# SCH_LED-Chaser_2025-12-01.net
KiCad netlist of a schematic drawn in EasyEDA
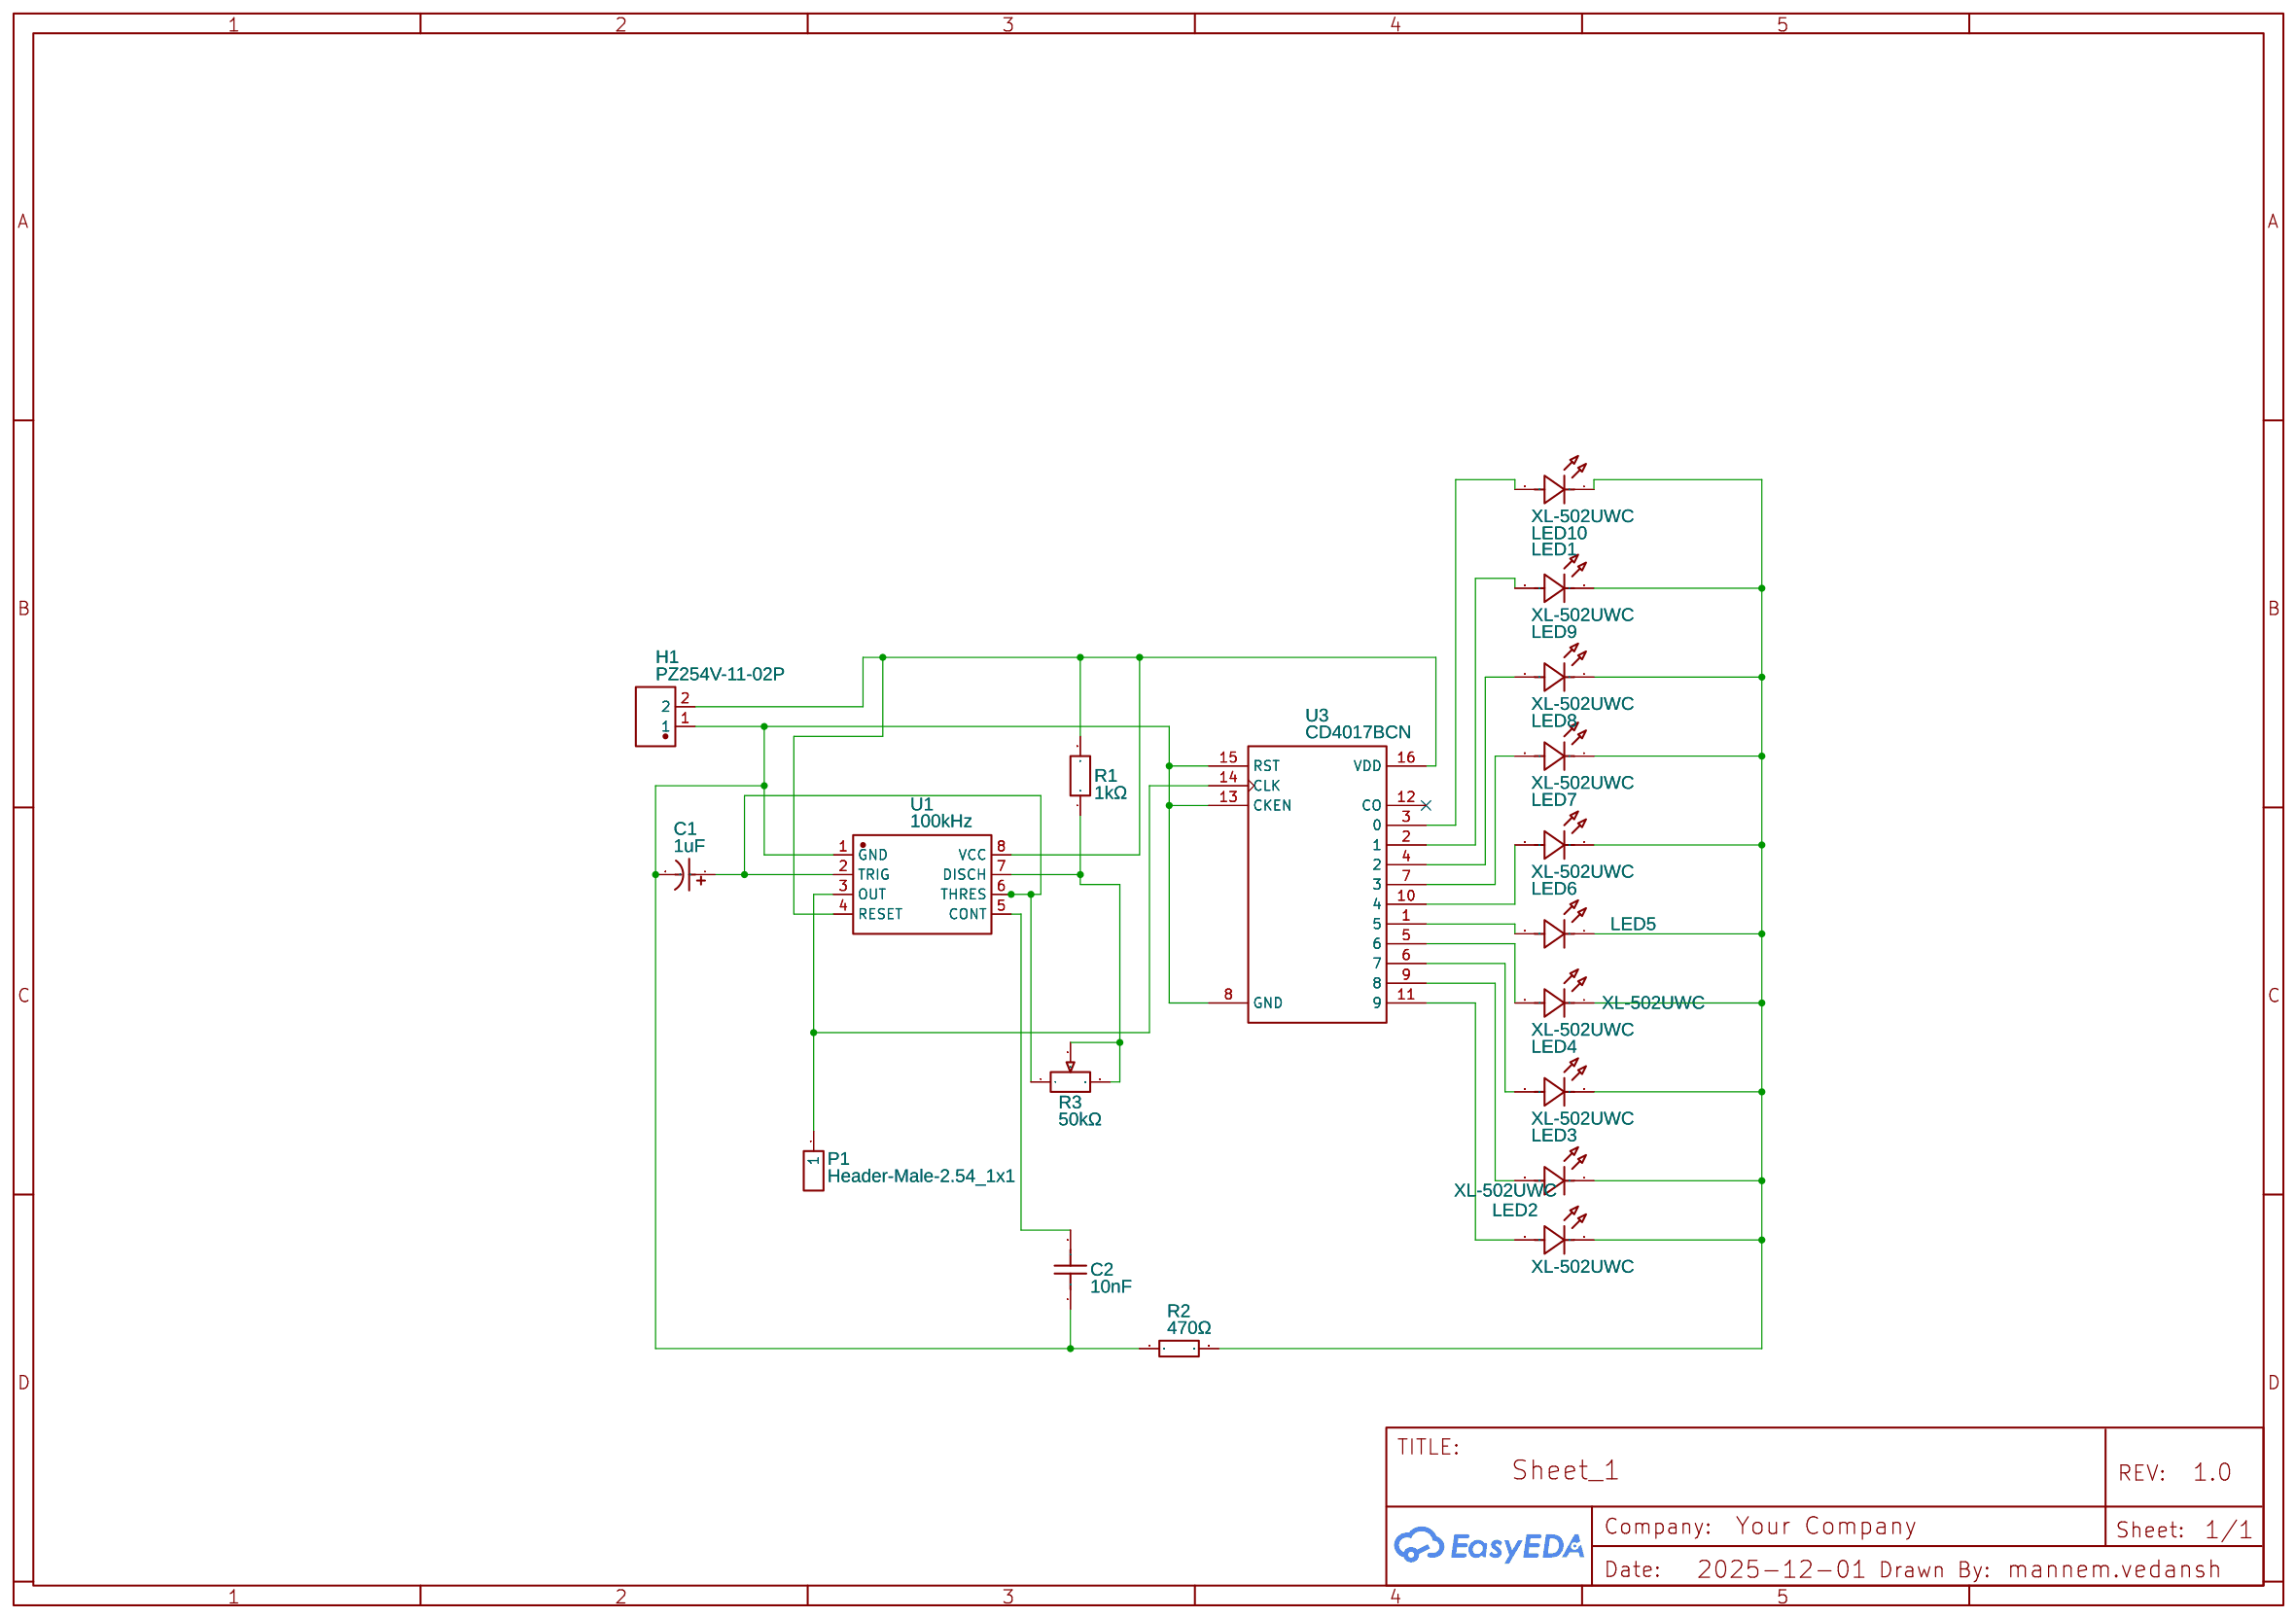
[diagram p0: schematic sheet]

(export (version "E")
  (design (tool "Eeschema 10.0.6"))
  (components
    (comp (ref "C1")
      (value "1uF")
      (fields (field (name "Manufacturer Part") "KF010M050C110A") (field (name "Manufacturer") "CapXon(丰宾)"))
      (libsource (lib "") (part "KF010M050C110A"))
    )
    (comp (ref "C2")
      (value "10nF")
      (fields (field (name "Manufacturer Part") "N09F1B103MN0B0S0N0") (field (name "Manufacturer") "STE(松田)"))
      (libsource (lib "") (part "N09F1B103MN0B0S0N0"))
    )
    (comp (ref "H1")
      (value "PZ254V-11-02P")
      (fields (field (name "Manufacturer") "XFCN(兴飞)"))
      (libsource (lib "") (part "PZ254V-11-02P"))
    )
    (comp (ref "LED1")
      (value "XL-502UWC")
      (fields (field (name "Manufacturer") "XINGLIGHT(成兴光)"))
      (libsource (lib "") (part "XL-502UWC"))
    )
    (comp (ref "LED2")
      (value "XL-502UWC")
      (fields (field (name "Manufacturer") "XINGLIGHT(成兴光)"))
      (libsource (lib "") (part "XL-502UWC"))
    )
    (comp (ref "LED3")
      (value "XL-502UWC")
      (fields (field (name "Manufacturer") "XINGLIGHT(成兴光)"))
      (libsource (lib "") (part "XL-502UWC"))
    )
    (comp (ref "LED4")
      (value "XL-502UWC")
      (fields (field (name "Manufacturer") "XINGLIGHT(成兴光)"))
      (libsource (lib "") (part "XL-502UWC"))
    )
    (comp (ref "LED5")
      (value "XL-502UWC")
      (fields (field (name "Manufacturer") "XINGLIGHT(成兴光)"))
      (libsource (lib "") (part "XL-502UWC"))
    )
    (comp (ref "LED6")
      (value "XL-502UWC")
      (fields (field (name "Manufacturer") "XINGLIGHT(成兴光)"))
      (libsource (lib "") (part "XL-502UWC"))
    )
    (comp (ref "LED7")
      (value "XL-502UWC")
      (fields (field (name "Manufacturer") "XINGLIGHT(成兴光)"))
      (libsource (lib "") (part "XL-502UWC"))
    )
    (comp (ref "LED8")
      (value "XL-502UWC")
      (fields (field (name "Manufacturer") "XINGLIGHT(成兴光)"))
      (libsource (lib "") (part "XL-502UWC"))
    )
    (comp (ref "LED9")
      (value "XL-502UWC")
      (fields (field (name "Manufacturer") "XINGLIGHT(成兴光)"))
      (libsource (lib "") (part "XL-502UWC"))
    )
    (comp (ref "LED10")
      (value "XL-502UWC")
      (fields (field (name "Manufacturer") "XINGLIGHT(成兴光)"))
      (libsource (lib "") (part "XL-502UWC"))
    )
    (comp (ref "P1")
      (value "Header-Male-2.54_1x1")
      (fields (field (name "Manufacturer Part") "2.54-1*1P针") (field (name "Manufacturer") "BOOMELE(博穆精密)"))
      (libsource (lib "") (part "Header-Male-2.54_1x1"))
    )
    (comp (ref "R1")
      (value "1kΩ")
      (fields (field (name "Manufacturer Part") "MF1/4W-1KΩ±1%T52") (field (name "Manufacturer") "华星机电"))
      (libsource (lib "") (part "MF1/4W-1KΩ±1%T52"))
    )
    (comp (ref "R2")
      (value "470Ω")
      (fields
        (field (name "Manufacturer Part") "MFR0W4F4700A50")
        (field (name "Manufacturer") "UNI-ROYAL(厚声)")
      )
      (libsource (lib "") (part "MFR0W4F4700A50"))
    )
    (comp (ref "R3")
      (value "50kΩ")
      (fields (field (name "Manufacturer Part") "3296X-1-503") (field (name "Manufacturer") "BOCHEN(博晨)"))
      (libsource (lib "") (part "3296X-1-503_C118912"))
    )
    (comp (ref "U1")
      (value "100kHz")
      (fields (field (name "Manufacturer Part") "NE555P") (field (name "Manufacturer") "TI(德州仪器)"))
      (libsource (lib "") (part "NE555P"))
    )
    (comp (ref "U3") (value "CD4017BCN") (libsource (lib "") (part "CD4017BCN")))
  )
  (nets
    (net (code "1") (name "Net-(LED1-A)") (class "Default")
      (node (ref "LED1") (pin "2") (pinfunction "A_2") (pintype "unspecified"))
      (node (ref "U3") (pin "11") (pinfunction "9_11") (pintype "output"))
    )
    (net (code "2") (name "Net-(LED1-K)") (class "Default")
      (node (ref "LED1") (pin "1") (pinfunction "K_1") (pintype "unspecified"))
      (node (ref "LED10") (pin "1") (pinfunction "K_1") (pintype "unspecified"))
      (node (ref "LED2") (pin "1") (pinfunction "K_1") (pintype "unspecified"))
      (node (ref "LED3") (pin "1") (pinfunction "K_1") (pintype "unspecified"))
      (node (ref "LED4") (pin "1") (pinfunction "K_1") (pintype "unspecified"))
      (node (ref "LED5") (pin "1") (pinfunction "K_1") (pintype "unspecified"))
      (node (ref "LED6") (pin "1") (pinfunction "K_1") (pintype "unspecified"))
      (node (ref "LED7") (pin "1") (pinfunction "K_1") (pintype "unspecified"))
      (node (ref "LED8") (pin "1") (pinfunction "K_1") (pintype "unspecified"))
      (node (ref "LED9") (pin "1") (pinfunction "K_1") (pintype "unspecified"))
      (node (ref "R2") (pin "2") (pinfunction "2_2") (pintype "input"))
    )
    (net (code "3") (name "Net-(LED2-A)") (class "Default")
      (node (ref "LED2") (pin "2") (pinfunction "A_2") (pintype "unspecified"))
      (node (ref "U3") (pin "9") (pinfunction "8_9") (pintype "output"))
    )
    (net (code "4") (name "Net-(LED3-A)") (class "Default")
      (node (ref "LED3") (pin "2") (pinfunction "A_2") (pintype "unspecified"))
      (node (ref "U3") (pin "6") (pinfunction "7_6") (pintype "output"))
    )
    (net (code "5") (name "Net-(LED4-A)") (class "Default")
      (node (ref "LED4") (pin "2") (pinfunction "A_2") (pintype "unspecified"))
      (node (ref "U3") (pin "5") (pinfunction "6_5") (pintype "output"))
    )
    (net (code "6") (name "Net-(LED5-A)") (class "Default")
      (node (ref "LED5") (pin "2") (pinfunction "A_2") (pintype "unspecified"))
      (node (ref "U3") (pin "1") (pinfunction "5_1") (pintype "output"))
    )
    (net (code "7") (name "Net-(LED6-A)") (class "Default")
      (node (ref "LED6") (pin "2") (pinfunction "A_2") (pintype "unspecified"))
      (node (ref "U3") (pin "10") (pinfunction "4_10") (pintype "output"))
    )
    (net (code "8") (name "Net-(LED7-A)") (class "Default")
      (node (ref "LED7") (pin "2") (pinfunction "A_2") (pintype "unspecified"))
      (node (ref "U3") (pin "7") (pinfunction "3_7") (pintype "output"))
    )
    (net (code "9") (name "Net-(LED8-A)") (class "Default")
      (node (ref "LED8") (pin "2") (pinfunction "A_2") (pintype "unspecified"))
      (node (ref "U3") (pin "4") (pinfunction "2_4") (pintype "output"))
    )
    (net (code "10") (name "Net-(LED9-A)") (class "Default")
      (node (ref "LED9") (pin "2") (pinfunction "A_2") (pintype "unspecified"))
      (node (ref "U3") (pin "2") (pinfunction "1_2") (pintype "output"))
    )
    (net (code "11") (name "Net-(LED10-A)") (class "Default")
      (node (ref "LED10") (pin "2") (pinfunction "A_2") (pintype "unspecified"))
      (node (ref "U3") (pin "3") (pinfunction "0_3") (pintype "output"))
    )
    (net (code "12") (name "Net-(U1-CONT)") (class "Default")
      (node (ref "C2") (pin "2") (pinfunction "2_2") (pintype "unspecified"))
      (node (ref "U1") (pin "5") (pinfunction "CONT_5") (pintype "unspecified"))
    )
    (net (code "13") (name "Net-(U1-DISCH)") (class "Default")
      (node (ref "R1") (pin "1") (pinfunction "1_1") (pintype "unspecified"))
      (node (ref "R3") (pin "2") (pinfunction "2_2") (pintype "input"))
      (node (ref "R3") (pin "3") (pinfunction "3_3") (pintype "input"))
      (node (ref "U1") (pin "7") (pinfunction "DISCH_7") (pintype "unspecified"))
    )
    (net (code "14") (name "Net-(U1-GND)") (class "Default")
      (node (ref "C1") (pin "2") (pinfunction "2_2") (pintype "input"))
      (node (ref "C2") (pin "1") (pinfunction "1_1") (pintype "unspecified"))
      (node (ref "H1") (pin "1") (pinfunction "1_1") (pintype "unspecified"))
      (node (ref "R2") (pin "1") (pinfunction "1_1") (pintype "input"))
      (node (ref "U1") (pin "1") (pinfunction "GND_1") (pintype "unspecified"))
      (node (ref "U3") (pin "13") (pinfunction "CKEN_13") (pintype "unspecified"))
      (node (ref "U3") (pin "15") (pinfunction "RST_15") (pintype "unspecified"))
      (node (ref "U3") (pin "8") (pinfunction "GND_8") (pintype "passive"))
    )
    (net (code "15") (name "Net-(U1-OUT)") (class "Default")
      (node (ref "P1") (pin "1") (pinfunction "1_1") (pintype "input"))
      (node (ref "U1") (pin "3") (pinfunction "OUT_3") (pintype "unspecified"))
      (node (ref "U3") (pin "14") (pinfunction "CLK_14") (pintype "unspecified"))
    )
    (net (code "16") (name "Net-(U1-RESET)") (class "Default")
      (node (ref "H1") (pin "2") (pinfunction "2_2") (pintype "unspecified"))
      (node (ref "R1") (pin "2") (pinfunction "2_2") (pintype "unspecified"))
      (node (ref "U1") (pin "4") (pinfunction "RESET_4") (pintype "unspecified"))
      (node (ref "U1") (pin "8") (pinfunction "VCC_8") (pintype "unspecified"))
      (node (ref "U3") (pin "16") (pinfunction "VDD_16") (pintype "passive"))
    )
    (net (code "17") (name "Net-(U1-THRES)") (class "Default")
      (node (ref "C1") (pin "1") (pinfunction "1_1") (pintype "input"))
      (node (ref "R3") (pin "1") (pinfunction "1_1") (pintype "input"))
      (node (ref "U1") (pin "2") (pinfunction "TRIG_2") (pintype "unspecified"))
      (node (ref "U1") (pin "6") (pinfunction "THRES_6") (pintype "unspecified"))
    )
    (net (code "18") (name "unconnected-(U3-CO-Pad12)") (class "Default")
      (node (ref "U3") (pin "12") (pinfunction "CO_12") (pintype "output+no_connect"))
    )
  )
)
